# ardunio-physics-board-v1.net
KiCad netlist of a schematic drawn in EAGLE
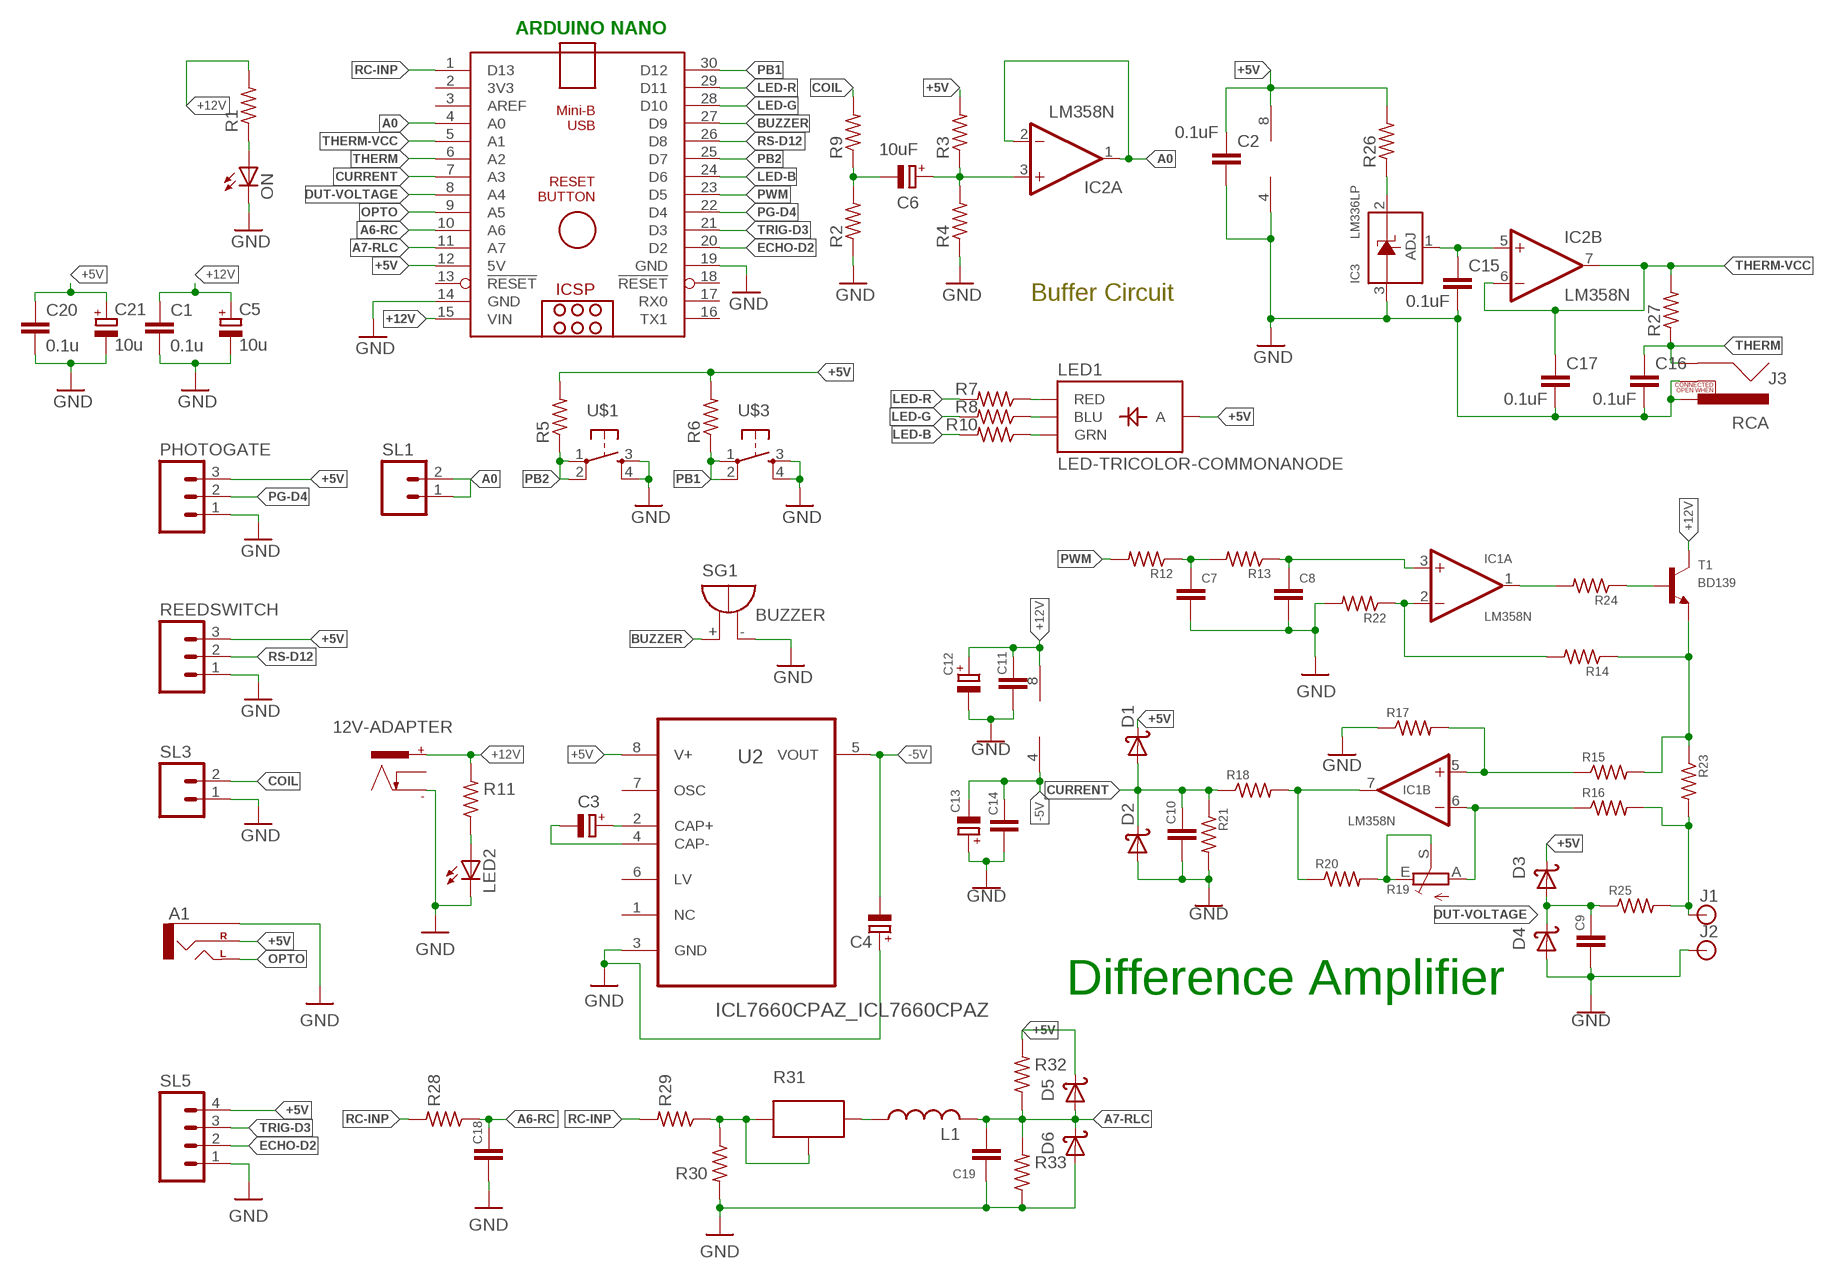
[diagram p0: schematic, sheet 1]

(export (version "E")
  (design (tool "Eeschema 10.0.6"))
  (components
    (comp (ref "12V-ADAPTER")
      (value "POWER_CON")
      (footprint "eagle-import:NEB21R")
      (libsource (lib "eagle-import") (part "POWER_CON"))
    )
    (comp (ref "A1")
      (value "CEDT_JANUARY_2015_V5_AUDIO-JACKPTH")
      (footprint "eagle-import:CEDT_JANUARY_2015_V5_AUDIO-JACK")
      (libsource (lib "eagle-import") (part "CEDT_JANUARY_2015_V5_AUDIO-JACKPTH"))
    )
    (comp (ref "ARDUINO_NANO1")
      (value "ARDUINO_NANO")
      (footprint "eagle-import:ARDUINO_NANO")
      (libsource (lib "eagle-import") (part "ARDUINO_NANO"))
    )
    (comp (ref "C1")
      (value "0.1u")
      (footprint "eagle-import:C025-024X044")
      (libsource (lib "eagle-import") (part "rcl_334_C-EU025-024X044"))
    )
    (comp (ref "C2")
      (value "0.1uF")
      (footprint "eagle-import:C025-025X050")
      (libsource (lib "eagle-import") (part "C-EU025-025X050"))
    )
    (comp (ref "C3")
      (value "CPOL-EUTT2D5")
      (footprint "eagle-import:TT2D5")
      (libsource (lib "eagle-import") (part "CPOL-EUTT2D5"))
    )
    (comp (ref "C4")
      (value "CPOL-EUTT2D5")
      (footprint "eagle-import:TT2D5")
      (libsource (lib "eagle-import") (part "CPOL-EUTT2D5"))
    )
    (comp (ref "C5")
      (value "10u")
      (footprint "eagle-import:E2,5-5")
      (libsource (lib "eagle-import") (part "CPOL-EUE2.5-5"))
    )
    (comp (ref "C6")
      (value "10uF")
      (footprint "eagle-import:E2,5-6")
      (libsource (lib "eagle-import") (part "CPOL-EUE2.5-6"))
    )
    (comp (ref "C7")
      (value "C-EU025-025X050")
      (footprint "eagle-import:C025-025X050")
      (libsource (lib "eagle-import") (part "rcl_334_C-EU025-025X050"))
    )
    (comp (ref "C8")
      (value "C-EU025-025X050")
      (footprint "eagle-import:C025-025X050")
      (libsource (lib "eagle-import") (part "rcl_334_C-EU025-025X050"))
    )
    (comp (ref "C9")
      (value "C-EU025-025X050")
      (footprint "eagle-import:C025-025X050")
      (libsource (lib "eagle-import") (part "rcl_334_C-EU025-025X050"))
    )
    (comp (ref "C10")
      (value "C-EU025-025X050")
      (footprint "eagle-import:C025-025X050")
      (libsource (lib "eagle-import") (part "rcl_334_C-EU025-025X050"))
    )
    (comp (ref "C11")
      (value "C-EU025-025X050")
      (footprint "eagle-import:C025-025X050")
      (libsource (lib "eagle-import") (part "rcl_334_C-EU025-025X050"))
    )
    (comp (ref "C12")
      (value "CPOL-EUTT2D5")
      (footprint "eagle-import:TT2D5")
      (libsource (lib "eagle-import") (part "CPOL-EUTT2D5"))
    )
    (comp (ref "C13")
      (value "CPOL-EUTT2D5")
      (footprint "eagle-import:TT2D5")
      (libsource (lib "eagle-import") (part "CPOL-EUTT2D5"))
    )
    (comp (ref "C14")
      (value "C-EU025-025X050")
      (footprint "eagle-import:C025-025X050")
      (libsource (lib "eagle-import") (part "rcl_334_C-EU025-025X050"))
    )
    (comp (ref "C15")
      (value "0.1uF")
      (footprint "eagle-import:C025-025X050")
      (libsource (lib "eagle-import") (part "C-EU025-025X050"))
    )
    (comp (ref "C16")
      (value "0.1uF")
      (footprint "eagle-import:C025-025X050")
      (libsource (lib "eagle-import") (part "C-EU025-025X050"))
    )
    (comp (ref "C17")
      (value "0.1uF")
      (footprint "eagle-import:C025-025X050")
      (libsource (lib "eagle-import") (part "C-EU025-025X050"))
    )
    (comp (ref "C18")
      (value "C-EU025-025X050")
      (footprint "eagle-import:C025-025X050")
      (libsource (lib "eagle-import") (part "rcl_334_C-EU025-025X050"))
    )
    (comp (ref "C19")
      (value "C-EU025-025X050")
      (footprint "eagle-import:C025-025X050")
      (libsource (lib "eagle-import") (part "rcl_334_C-EU025-025X050"))
    )
    (comp (ref "C20")
      (value "0.1u")
      (footprint "eagle-import:C025-024X044")
      (libsource (lib "eagle-import") (part "rcl_334_C-EU025-024X044"))
    )
    (comp (ref "C21")
      (value "10u")
      (footprint "eagle-import:E2,5-5")
      (libsource (lib "eagle-import") (part "CPOL-EUE2.5-5"))
    )
    (comp (ref "D1")
      (value "1N5819")
      (footprint "eagle-import:DO41-10")
      (libsource (lib "eagle-import") (part "1N5819"))
    )
    (comp (ref "D2")
      (value "1N5819")
      (footprint "eagle-import:DO41-10")
      (libsource (lib "eagle-import") (part "1N5819"))
    )
    (comp (ref "D3")
      (value "1N5819")
      (footprint "eagle-import:DO41-10")
      (libsource (lib "eagle-import") (part "1N5819"))
    )
    (comp (ref "D4")
      (value "1N5819")
      (footprint "eagle-import:DO41-10")
      (libsource (lib "eagle-import") (part "1N5819"))
    )
    (comp (ref "D5")
      (value "1N5819")
      (footprint "eagle-import:DO41-10")
      (libsource (lib "eagle-import") (part "1N5819"))
    )
    (comp (ref "D6")
      (value "1N5819")
      (footprint "eagle-import:DO41-10")
      (libsource (lib "eagle-import") (part "1N5819"))
    )
    (comp (ref "IC1")
      (value "LM358N")
      (footprint "eagle-import:DIL08")
      (libsource (lib "eagle-import") (part "LM358N"))
    )
    (comp (ref "IC2")
      (value "LM358N")
      (footprint "eagle-import:DIL08")
      (libsource (lib "eagle-import") (part "LM358N"))
    )
    (comp (ref "IC3")
      (value "LM336LP")
      (footprint "eagle-import:TO92")
      (libsource (lib "eagle-import") (part "LM336LP"))
    )
    (comp (ref "J1")
      (value "BANANA_CONN")
      (footprint "eagle-import:BANANA_CONN")
      (libsource (lib "eagle-import") (part "BANANA_CONN"))
    )
    (comp (ref "J2")
      (value "BANANA_CONN")
      (footprint "eagle-import:BANANA_CONN")
      (libsource (lib "eagle-import") (part "BANANA_CONN"))
    )
    (comp (ref "J3")
      (value "RCA")
      (footprint "eagle-import:RCA")
      (libsource (lib "eagle-import") (part "RCA"))
    )
    (comp (ref "L1")
      (value "L-US6000-XXX-RC")
      (footprint "eagle-import:6000-XXXX-RC")
      (libsource (lib "eagle-import") (part "L-US6000-XXX-RC"))
    )
    (comp (ref "LED1")
      (value "LED-TRICOLOR-COMMONANODE")
      (footprint "eagle-import:LED-TRICOLOR-THROUGHHOLE")
      (libsource (lib "eagle-import") (part "LED-TRICOLOR-COMMONANODE"))
    )
    (comp (ref "LED2")
      (value "LED3MM")
      (footprint "eagle-import:LED3MM")
      (libsource (lib "eagle-import") (part "CEDT_JANUARY_2015_v5_LED3MM"))
    )
    (comp (ref "ON")
      (value "LED3MM")
      (footprint "eagle-import:LED3MM")
      (libsource (lib "eagle-import") (part "LED3MM"))
    )
    (comp (ref "PHOTOGATE")
      (value "M03")
      (footprint "eagle-import:03P")
      (libsource (lib "eagle-import") (part "M03"))
    )
    (comp (ref "R1")
      (value "R-US_0204/7")
      (footprint "eagle-import:0204_7")
      (libsource (lib "eagle-import") (part "R-US_0204/7"))
    )
    (comp (ref "R2")
      (value "R-US_0204/7")
      (footprint "eagle-import:0204_7")
      (libsource (lib "eagle-import") (part "R-US_0204/7"))
    )
    (comp (ref "R3")
      (value "R-US_0204/7")
      (footprint "eagle-import:0204_7")
      (libsource (lib "eagle-import") (part "R-US_0204/7"))
    )
    (comp (ref "R4")
      (value "R-US_0204/7")
      (footprint "eagle-import:0204_7")
      (libsource (lib "eagle-import") (part "R-US_0204/7"))
    )
    (comp (ref "R5")
      (value "R-US_0204/7")
      (footprint "eagle-import:0204_7")
      (libsource (lib "eagle-import") (part "R-US_0204/7"))
    )
    (comp (ref "R6")
      (value "R-US_0204/7")
      (footprint "eagle-import:0204_7")
      (libsource (lib "eagle-import") (part "R-US_0204/7"))
    )
    (comp (ref "R7")
      (value "R-US_0204/7")
      (footprint "eagle-import:0204_7")
      (libsource (lib "eagle-import") (part "R-US_0204/7"))
    )
    (comp (ref "R8")
      (value "R-US_0204/7")
      (footprint "eagle-import:0204_7")
      (libsource (lib "eagle-import") (part "R-US_0204/7"))
    )
    (comp (ref "R9")
      (value "R-US_0204/7")
      (footprint "eagle-import:0204_7")
      (libsource (lib "eagle-import") (part "R-US_0204/7"))
    )
    (comp (ref "R10")
      (value "R-US_0204/7")
      (footprint "eagle-import:0204_7")
      (libsource (lib "eagle-import") (part "R-US_0204/7"))
    )
    (comp (ref "R11")
      (value "R-US_0204/7")
      (footprint "eagle-import:0204_7")
      (libsource (lib "eagle-import") (part "R-US_0204/7"))
    )
    (comp (ref "R12")
      (value "R-US_0204/7")
      (footprint "eagle-import:0204_7")
      (libsource (lib "eagle-import") (part "R-US_0204/7"))
    )
    (comp (ref "R13")
      (value "R-US_0204/7")
      (footprint "eagle-import:0204_7")
      (libsource (lib "eagle-import") (part "R-US_0204/7"))
    )
    (comp (ref "R14")
      (value "R-US_0204/7")
      (footprint "eagle-import:0204_7")
      (libsource (lib "eagle-import") (part "R-US_0204/7"))
    )
    (comp (ref "R15")
      (value "R-US_0204/7")
      (footprint "eagle-import:0204_7")
      (libsource (lib "eagle-import") (part "R-US_0204/7"))
    )
    (comp (ref "R16")
      (value "R-US_0204/7")
      (footprint "eagle-import:0204_7")
      (libsource (lib "eagle-import") (part "R-US_0204/7"))
    )
    (comp (ref "R17")
      (value "R-US_0204/7")
      (footprint "eagle-import:0204_7")
      (libsource (lib "eagle-import") (part "R-US_0204/7"))
    )
    (comp (ref "R18")
      (value "R-US_0204/7")
      (footprint "eagle-import:0204_7")
      (libsource (lib "eagle-import") (part "R-US_0204/7"))
    )
    (comp (ref "R19")
      (value "TRIM_EU-RJ9W")
      (footprint "eagle-import:RJ9W")
      (libsource (lib "eagle-import") (part "TRIM_EU-RJ9W"))
    )
    (comp (ref "R20")
      (value "R-US_0204/7")
      (footprint "eagle-import:0204_7")
      (libsource (lib "eagle-import") (part "R-US_0204/7"))
    )
    (comp (ref "R21")
      (value "R-US_0204/7")
      (footprint "eagle-import:0204_7")
      (libsource (lib "eagle-import") (part "R-US_0204/7"))
    )
    (comp (ref "R22")
      (value "R-US_0204/7")
      (footprint "eagle-import:0204_7")
      (libsource (lib "eagle-import") (part "R-US_0204/7"))
    )
    (comp (ref "R23")
      (value "R-US_0207/10")
      (footprint "eagle-import:0207_10")
      (libsource (lib "eagle-import") (part "R-US_0207/10"))
    )
    (comp (ref "R24")
      (value "R-US_0204/7")
      (footprint "eagle-import:0204_7")
      (libsource (lib "eagle-import") (part "R-US_0204/7"))
    )
    (comp (ref "R25")
      (value "R-US_0204/7")
      (footprint "eagle-import:0204_7")
      (libsource (lib "eagle-import") (part "R-US_0204/7"))
    )
    (comp (ref "R26")
      (value "R-US_0204/7")
      (footprint "eagle-import:0204_7")
      (libsource (lib "eagle-import") (part "R-US_0204/7"))
    )
    (comp (ref "R27")
      (value "R-US_0204/7")
      (footprint "eagle-import:0204_7")
      (libsource (lib "eagle-import") (part "R-US_0204/7"))
    )
    (comp (ref "R28")
      (value "R-US_0204/7")
      (footprint "eagle-import:0204_7")
      (libsource (lib "eagle-import") (part "R-US_0204/7"))
    )
    (comp (ref "R29")
      (value "R-US_0204/7")
      (footprint "eagle-import:0204_7")
      (libsource (lib "eagle-import") (part "R-US_0204/7"))
    )
    (comp (ref "R30")
      (value "R-US_0204/7")
      (footprint "eagle-import:0204_7")
      (libsource (lib "eagle-import") (part "R-US_0204/7"))
    )
    (comp (ref "R31")
      (value "POTNORMAL")
      (footprint "eagle-import:RJ9W")
      (libsource (lib "eagle-import") (part "POTNORMAL"))
    )
    (comp (ref "R32")
      (value "R-US_0204/7")
      (footprint "eagle-import:0204_7")
      (libsource (lib "eagle-import") (part "R-US_0204/7"))
    )
    (comp (ref "R33")
      (value "R-US_0204/7")
      (footprint "eagle-import:0204_7")
      (libsource (lib "eagle-import") (part "R-US_0204/7"))
    )
    (comp (ref "REEDSWITCH")
      (value "M03")
      (footprint "eagle-import:03P")
      (libsource (lib "eagle-import") (part "M03"))
    )
    (comp (ref "SG1")
      (value "BUZZER")
      (footprint "eagle-import:F_TMB")
      (libsource (lib "eagle-import") (part "BUZZER"))
    )
    (comp (ref "SL1")
      (value "M02")
      (footprint "eagle-import:02P")
      (libsource (lib "eagle-import") (part "M02"))
    )
    (comp (ref "SL3")
      (value "M02")
      (footprint "eagle-import:02P")
      (libsource (lib "eagle-import") (part "M02"))
    )
    (comp (ref "SL5")
      (value "M04")
      (footprint "eagle-import:04P")
      (libsource (lib "eagle-import") (part "M04"))
    )
    (comp (ref "T1")
      (value "BD139")
      (footprint "eagle-import:TO126")
      (libsource (lib "eagle-import") (part "BD139"))
    )
    (comp (ref "U$1")
      (value "OMRON_SWITCH_40-XX")
      (footprint "eagle-import:B3F-40XX")
      (libsource (lib "eagle-import") (part "OMRON_SWITCH_40-XX"))
    )
    (comp (ref "U$3")
      (value "OMRON_SWITCH_40-XX")
      (footprint "eagle-import:B3F-40XX")
      (libsource (lib "eagle-import") (part "OMRON_SWITCH_40-XX"))
    )
    (comp (ref "U2")
      (value "ICL7660CPAZ_ICL7660CPAZ")
      (footprint "eagle-import:ICL7660CPAZ_DIP254P762X533-8")
      (fields (field (name "MF") "Renesas Electronics") (field (name "MP") "ICL7660CPAZ"))
      (libsource (lib "eagle-import") (part "ICL7660CPAZ_ICL7660CPAZ"))
    )
  )
  (nets
    (net (code "1") (name "+5V") (class "Default")
      (node (ref "A1") (pin "RING") (pinfunction "RIGHT_RING") (pintype "bidirectional"))
      (node (ref "ARDUINO_NANO1") (pin "12") (pinfunction "5V_12") (pintype "power_in"))
      (node (ref "C2") (pin "1") (pinfunction "1_1") (pintype "passive"))
      (node (ref "C20") (pin "1") (pinfunction "1_1") (pintype "passive"))
      (node (ref "C21") (pin "+") (pinfunction "+_+") (pintype "passive"))
      (node (ref "D1") (pin "C") (pinfunction "C_C") (pintype "passive"))
      (node (ref "D3") (pin "C") (pinfunction "C_C") (pintype "passive"))
      (node (ref "D5") (pin "C") (pinfunction "C_C") (pintype "passive"))
      (node (ref "IC2") (pin "8") (pinfunction "V+_8") (pintype "power_in"))
      (node (ref "LED1") (pin "ANODE") (pinfunction "A_ANODE") (pintype "bidirectional"))
      (node (ref "PHOTOGATE") (pin "3") (pinfunction "3_3") (pintype "passive"))
      (node (ref "R26") (pin "2") (pinfunction "2_2") (pintype "passive"))
      (node (ref "R3") (pin "2") (pinfunction "2_2") (pintype "passive"))
      (node (ref "R32") (pin "2") (pinfunction "2_2") (pintype "passive"))
      (node (ref "R5") (pin "2") (pinfunction "2_2") (pintype "passive"))
      (node (ref "R6") (pin "2") (pinfunction "2_2") (pintype "passive"))
      (node (ref "REEDSWITCH") (pin "3") (pinfunction "3_3") (pintype "passive"))
      (node (ref "SL5") (pin "4") (pinfunction "4_4") (pintype "passive"))
      (node (ref "U2") (pin "8") (pinfunction "V+_8") (pintype "power_in"))
    )
    (net (code "2") (name "+12V") (class "Default")
      (node (ref "12V-ADAPTER") (pin "+") (pinfunction "+_+") (pintype "passive"))
      (node (ref "ARDUINO_NANO1") (pin "15") (pinfunction "VIN_15") (pintype "power_in"))
      (node (ref "C1") (pin "1") (pinfunction "1_1") (pintype "passive"))
      (node (ref "C11") (pin "1") (pinfunction "1_1") (pintype "passive"))
      (node (ref "C12") (pin "+") (pinfunction "+_+") (pintype "passive"))
      (node (ref "C5") (pin "+") (pinfunction "+_+") (pintype "passive"))
      (node (ref "IC1") (pin "8") (pinfunction "V+_8") (pintype "power_in"))
      (node (ref "R1") (pin "2") (pinfunction "2_2") (pintype "passive"))
      (node (ref "R11") (pin "2") (pinfunction "2_2") (pintype "passive"))
      (node (ref "T1") (pin "2") (pinfunction "C_2") (pintype "passive"))
    )
    (net (code "3") (name "-5V") (class "Default")
      (node (ref "C13") (pin "-") (pinfunction "-_-") (pintype "passive"))
      (node (ref "C14") (pin "1") (pinfunction "1_1") (pintype "passive"))
      (node (ref "C4") (pin "-") (pinfunction "-_-") (pintype "passive"))
      (node (ref "IC1") (pin "4") (pinfunction "V-_4") (pintype "power_in"))
      (node (ref "U2") (pin "5") (pinfunction "VOUT_5") (pintype "output"))
    )
    (net (code "4") (name "A0") (class "Default")
      (node (ref "ARDUINO_NANO1") (pin "4") (pinfunction "A0_4") (pintype "bidirectional"))
      (node (ref "IC2") (pin "1") (pinfunction "OUT_1") (pintype "output"))
      (node (ref "IC2") (pin "2") (pinfunction "-IN_2") (pintype "input"))
      (node (ref "SL1") (pin "1") (pinfunction "1_1") (pintype "passive"))
      (node (ref "SL1") (pin "2") (pinfunction "2_2") (pintype "passive"))
    )
    (net (code "5") (name "A6-RC") (class "Default")
      (node (ref "ARDUINO_NANO1") (pin "10") (pinfunction "A6_10") (pintype "bidirectional"))
      (node (ref "C18") (pin "1") (pinfunction "1_1") (pintype "passive"))
      (node (ref "R28") (pin "1") (pinfunction "1_1") (pintype "passive"))
    )
    (net (code "6") (name "A7-RLC") (class "Default")
      (node (ref "ARDUINO_NANO1") (pin "11") (pinfunction "A7_11") (pintype "bidirectional"))
      (node (ref "C19") (pin "1") (pinfunction "1_1") (pintype "passive"))
      (node (ref "D5") (pin "A") (pinfunction "A_A") (pintype "passive"))
      (node (ref "D6") (pin "C") (pinfunction "C_C") (pintype "passive"))
      (node (ref "L1") (pin "2") (pinfunction "2_2") (pintype "passive"))
      (node (ref "R32") (pin "1") (pinfunction "1_1") (pintype "passive"))
      (node (ref "R33") (pin "2") (pinfunction "2_2") (pintype "passive"))
    )
    (net (code "7") (name "BUZZER") (class "Default")
      (node (ref "ARDUINO_NANO1") (pin "27") (pinfunction "D9_27") (pintype "bidirectional"))
      (node (ref "SG1") (pin "+") (pinfunction "+_+") (pintype "passive"))
    )
    (net (code "8") (name "COIL") (class "Default")
      (node (ref "R9") (pin "2") (pinfunction "2_2") (pintype "passive"))
      (node (ref "SL3") (pin "2") (pinfunction "2_2") (pintype "passive"))
    )
    (net (code "9") (name "CURRENT") (class "Default")
      (node (ref "ARDUINO_NANO1") (pin "7") (pinfunction "A3_7") (pintype "bidirectional"))
      (node (ref "C10") (pin "1") (pinfunction "1_1") (pintype "passive"))
      (node (ref "D1") (pin "A") (pinfunction "A_A") (pintype "passive"))
      (node (ref "D2") (pin "C") (pinfunction "C_C") (pintype "passive"))
      (node (ref "R18") (pin "1") (pinfunction "1_1") (pintype "passive"))
      (node (ref "R21") (pin "1") (pinfunction "1_1") (pintype "passive"))
    )
    (net (code "10") (name "DUT-VOLTAGE") (class "Default")
      (node (ref "ARDUINO_NANO1") (pin "8") (pinfunction "A4_8") (pintype "bidirectional"))
      (node (ref "C9") (pin "1") (pinfunction "1_1") (pintype "passive"))
      (node (ref "D3") (pin "A") (pinfunction "A_A") (pintype "passive"))
      (node (ref "D4") (pin "C") (pinfunction "C_C") (pintype "passive"))
      (node (ref "R25") (pin "1") (pinfunction "1_1") (pintype "passive"))
    )
    (net (code "11") (name "ECHO-D2") (class "Default")
      (node (ref "ARDUINO_NANO1") (pin "20") (pinfunction "D2_20") (pintype "bidirectional"))
      (node (ref "SL5") (pin "2") (pinfunction "2_2") (pintype "passive"))
    )
    (net (code "12") (name "GND") (class "Default")
      (node (ref "12V-ADAPTER") (pin "-") (pinfunction "-_-") (pintype "passive"))
      (node (ref "A1") (pin "SLEEVE") (pinfunction "SLEEVE_SLEEVE") (pintype "bidirectional"))
      (node (ref "ARDUINO_NANO1") (pin "14") (pinfunction "GND_14") (pintype "power_in"))
      (node (ref "ARDUINO_NANO1") (pin "19") (pinfunction "GND_19") (pintype "power_in"))
      (node (ref "C1") (pin "2") (pinfunction "2_2") (pintype "passive"))
      (node (ref "C10") (pin "2") (pinfunction "2_2") (pintype "passive"))
      (node (ref "C11") (pin "2") (pinfunction "2_2") (pintype "passive"))
      (node (ref "C12") (pin "-") (pinfunction "-_-") (pintype "passive"))
      (node (ref "C13") (pin "+") (pinfunction "+_+") (pintype "passive"))
      (node (ref "C14") (pin "2") (pinfunction "2_2") (pintype "passive"))
      (node (ref "C15") (pin "2") (pinfunction "2_2") (pintype "passive"))
      (node (ref "C16") (pin "2") (pinfunction "2_2") (pintype "passive"))
      (node (ref "C17") (pin "2") (pinfunction "2_2") (pintype "passive"))
      (node (ref "C18") (pin "2") (pinfunction "2_2") (pintype "passive"))
      (node (ref "C19") (pin "2") (pinfunction "2_2") (pintype "passive"))
      (node (ref "C2") (pin "2") (pinfunction "2_2") (pintype "passive"))
      (node (ref "C20") (pin "2") (pinfunction "2_2") (pintype "passive"))
      (node (ref "C21") (pin "-") (pinfunction "-_-") (pintype "passive"))
      (node (ref "C4") (pin "+") (pinfunction "+_+") (pintype "passive"))
      (node (ref "C5") (pin "-") (pinfunction "-_-") (pintype "passive"))
      (node (ref "C7") (pin "2") (pinfunction "2_2") (pintype "passive"))
      (node (ref "C8") (pin "2") (pinfunction "2_2") (pintype "passive"))
      (node (ref "C9") (pin "2") (pinfunction "2_2") (pintype "passive"))
      (node (ref "D2") (pin "A") (pinfunction "A_A") (pintype "passive"))
      (node (ref "D4") (pin "A") (pinfunction "A_A") (pintype "passive"))
      (node (ref "D6") (pin "A") (pinfunction "A_A") (pintype "passive"))
      (node (ref "IC2") (pin "4") (pinfunction "V-_4") (pintype "power_in"))
      (node (ref "IC3") (pin "3") (pinfunction "A_3") (pintype "input"))
      (node (ref "J2") (pin "P$1") (pinfunction "1_P$1") (pintype "passive"))
      (node (ref "J3") (pin "PIN") (pinfunction "PIN_PIN") (pintype "bidirectional"))
      (node (ref "J3") (pin "SWITCH") (pinfunction "SWITCH_SWITCH") (pintype "bidirectional"))
      (node (ref "LED2") (pin "K") (pinfunction "C_K") (pintype "passive"))
      (node (ref "ON") (pin "K") (pinfunction "C_K") (pintype "passive"))
      (node (ref "PHOTOGATE") (pin "1") (pinfunction "1_1") (pintype "passive"))
      (node (ref "R17") (pin "1") (pinfunction "1_1") (pintype "passive"))
      (node (ref "R2") (pin "1") (pinfunction "1_1") (pintype "passive"))
      (node (ref "R21") (pin "2") (pinfunction "2_2") (pintype "passive"))
      (node (ref "R22") (pin "2") (pinfunction "2_2") (pintype "passive"))
      (node (ref "R30") (pin "2") (pinfunction "2_2") (pintype "passive"))
      (node (ref "R33") (pin "1") (pinfunction "1_1") (pintype "passive"))
      (node (ref "R4") (pin "1") (pinfunction "1_1") (pintype "passive"))
      (node (ref "REEDSWITCH") (pin "1") (pinfunction "1_1") (pintype "passive"))
      (node (ref "SG1") (pin "-") (pinfunction "-_-") (pintype "passive"))
      (node (ref "SL3") (pin "1") (pinfunction "1_1") (pintype "passive"))
      (node (ref "SL5") (pin "1") (pinfunction "1_1") (pintype "passive"))
      (node (ref "U$1") (pin "3") (pinfunction "S_3") (pintype "passive"))
      (node (ref "U$1") (pin "4") (pinfunction "S1_4") (pintype "passive"))
      (node (ref "U$3") (pin "3") (pinfunction "S_3") (pintype "passive"))
      (node (ref "U$3") (pin "4") (pinfunction "S1_4") (pintype "passive"))
      (node (ref "U2") (pin "3") (pinfunction "GND_3") (pintype "passive"))
    )
    (net (code "13") (name "LED-B") (class "Default")
      (node (ref "ARDUINO_NANO1") (pin "24") (pinfunction "D6_24") (pintype "bidirectional"))
      (node (ref "R10") (pin "2") (pinfunction "2_2") (pintype "passive"))
    )
    (net (code "14") (name "LED-G") (class "Default")
      (node (ref "ARDUINO_NANO1") (pin "28") (pinfunction "D10_28") (pintype "bidirectional"))
      (node (ref "R8") (pin "2") (pinfunction "2_2") (pintype "passive"))
    )
    (net (code "15") (name "LED-R") (class "Default")
      (node (ref "ARDUINO_NANO1") (pin "29") (pinfunction "D11_29") (pintype "bidirectional"))
      (node (ref "R7") (pin "2") (pinfunction "2_2") (pintype "passive"))
    )
    (net (code "16") (name "Net-(C6-Pad-)") (class "Default")
      (node (ref "C6") (pin "-") (pinfunction "-_-") (pintype "passive"))
      (node (ref "R2") (pin "2") (pinfunction "2_2") (pintype "passive"))
      (node (ref "R9") (pin "1") (pinfunction "1_1") (pintype "passive"))
    )
    (net (code "17") (name "Net-(C7-Pad1)") (class "Default")
      (node (ref "C7") (pin "1") (pinfunction "1_1") (pintype "passive"))
      (node (ref "R12") (pin "1") (pinfunction "1_1") (pintype "passive"))
      (node (ref "R13") (pin "2") (pinfunction "2_2") (pintype "passive"))
    )
    (net (code "18") (name "Net-(IC1A-+IN)") (class "Default")
      (node (ref "C8") (pin "1") (pinfunction "1_1") (pintype "passive"))
      (node (ref "IC1") (pin "3") (pinfunction "+IN_3") (pintype "input"))
      (node (ref "R13") (pin "1") (pinfunction "1_1") (pintype "passive"))
    )
    (net (code "19") (name "Net-(IC1A--IN)") (class "Default")
      (node (ref "IC1") (pin "2") (pinfunction "-IN_2") (pintype "input"))
      (node (ref "R14") (pin "2") (pinfunction "2_2") (pintype "passive"))
      (node (ref "R22") (pin "1") (pinfunction "1_1") (pintype "passive"))
    )
    (net (code "20") (name "Net-(IC1A-OUT)") (class "Default")
      (node (ref "IC1") (pin "1") (pinfunction "OUT_1") (pintype "output"))
      (node (ref "R24") (pin "2") (pinfunction "2_2") (pintype "passive"))
    )
    (net (code "21") (name "Net-(IC1B-+IN)") (class "Default")
      (node (ref "IC1") (pin "5") (pinfunction "+IN_5") (pintype "input"))
      (node (ref "R15") (pin "1") (pinfunction "1_1") (pintype "passive"))
      (node (ref "R17") (pin "2") (pinfunction "2_2") (pintype "passive"))
    )
    (net (code "22") (name "Net-(IC1B--IN)") (class "Default")
      (node (ref "IC1") (pin "6") (pinfunction "-IN_6") (pintype "input"))
      (node (ref "R16") (pin "1") (pinfunction "1_1") (pintype "passive"))
      (node (ref "R19") (pin "A") (pinfunction "A_A") (pintype "passive"))
    )
    (net (code "23") (name "Net-(IC1B-OUT)") (class "Default")
      (node (ref "IC1") (pin "7") (pinfunction "OUT_7") (pintype "output"))
      (node (ref "R18") (pin "2") (pinfunction "2_2") (pintype "passive"))
      (node (ref "R20") (pin "1") (pinfunction "1_1") (pintype "passive"))
    )
    (net (code "24") (name "Net-(IC2A-+IN)") (class "Default")
      (node (ref "C6") (pin "+") (pinfunction "+_+") (pintype "passive"))
      (node (ref "IC2") (pin "3") (pinfunction "+IN_3") (pintype "input"))
      (node (ref "R3") (pin "1") (pinfunction "1_1") (pintype "passive"))
      (node (ref "R4") (pin "2") (pinfunction "2_2") (pintype "passive"))
    )
    (net (code "25") (name "Net-(IC2B-+IN)") (class "Default")
      (node (ref "C15") (pin "1") (pinfunction "1_1") (pintype "passive"))
      (node (ref "IC2") (pin "5") (pinfunction "+IN_5") (pintype "input"))
      (node (ref "IC3") (pin "1") (pinfunction "ADJ_1") (pintype "input"))
    )
    (net (code "26") (name "Net-(IC3-C)") (class "Default")
      (node (ref "IC3") (pin "2") (pinfunction "C_2") (pintype "passive"))
      (node (ref "R26") (pin "1") (pinfunction "1_1") (pintype "passive"))
    )
    (net (code "27") (name "Net-(J1-1)") (class "Default")
      (node (ref "J1") (pin "P$1") (pinfunction "1_P$1") (pintype "passive"))
      (node (ref "R16") (pin "2") (pinfunction "2_2") (pintype "passive"))
      (node (ref "R23") (pin "2") (pinfunction "2_2") (pintype "passive"))
      (node (ref "R25") (pin "2") (pinfunction "2_2") (pintype "passive"))
    )
    (net (code "28") (name "Net-(L1-Pad1)") (class "Default")
      (node (ref "L1") (pin "1") (pinfunction "1_1") (pintype "passive"))
      (node (ref "R31") (pin "A") (pinfunction "A_A") (pintype "passive"))
    )
    (net (code "29") (name "Net-(LED1-PadBLU)") (class "Default")
      (node (ref "LED1") (pin "BLU") (pinfunction "BLU_BLU") (pintype "bidirectional"))
      (node (ref "R8") (pin "1") (pinfunction "1_1") (pintype "passive"))
    )
    (net (code "30") (name "Net-(LED1-PadGRN)") (class "Default")
      (node (ref "LED1") (pin "GRN") (pinfunction "GRN_GRN") (pintype "bidirectional"))
      (node (ref "R10") (pin "1") (pinfunction "1_1") (pintype "passive"))
    )
    (net (code "31") (name "Net-(LED1-PadRED)") (class "Default")
      (node (ref "LED1") (pin "RED") (pinfunction "RED_RED") (pintype "bidirectional"))
      (node (ref "R7") (pin "1") (pinfunction "1_1") (pintype "passive"))
    )
    (net (code "32") (name "Net-(LED2-PadA)") (class "Default")
      (node (ref "LED2") (pin "A") (pinfunction "A_A") (pintype "passive"))
      (node (ref "R11") (pin "1") (pinfunction "1_1") (pintype "passive"))
    )
    (net (code "33") (name "Net-(ON-PadA)") (class "Default")
      (node (ref "ON") (pin "A") (pinfunction "A_A") (pintype "passive"))
      (node (ref "R1") (pin "1") (pinfunction "1_1") (pintype "passive"))
    )
    (net (code "34") (name "Net-(R19-PadE)") (class "Default")
      (node (ref "R19") (pin "E") (pinfunction "E_E") (pintype "passive"))
      (node (ref "R19") (pin "S") (pinfunction "S_S") (pintype "passive"))
      (node (ref "R20") (pin "2") (pinfunction "2_2") (pintype "passive"))
    )
    (net (code "35") (name "Net-(R29-Pad1)") (class "Default")
      (node (ref "R29") (pin "1") (pinfunction "1_1") (pintype "passive"))
      (node (ref "R30") (pin "1") (pinfunction "1_1") (pintype "passive"))
      (node (ref "R31") (pin "E") (pinfunction "E_E") (pintype "passive"))
      (node (ref "R31") (pin "S") (pinfunction "S_S") (pintype "passive"))
    )
    (net (code "36") (name "Net-(T1-B)") (class "Default")
      (node (ref "R24") (pin "1") (pinfunction "1_1") (pintype "passive"))
      (node (ref "T1") (pin "3") (pinfunction "B_3") (pintype "passive"))
    )
    (net (code "37") (name "Net-(T1-E)") (class "Default")
      (node (ref "R14") (pin "1") (pinfunction "1_1") (pintype "passive"))
      (node (ref "R15") (pin "2") (pinfunction "2_2") (pintype "passive"))
      (node (ref "R23") (pin "1") (pinfunction "1_1") (pintype "passive"))
      (node (ref "T1") (pin "1") (pinfunction "E_1") (pintype "passive"))
    )
    (net (code "38") (name "Net-(U2-CAP+)") (class "Default")
      (node (ref "C3") (pin "+") (pinfunction "+_+") (pintype "passive"))
      (node (ref "U2") (pin "2") (pinfunction "CAP+_2") (pintype "input"))
    )
    (net (code "39") (name "Net-(U2-CAP-)") (class "Default")
      (node (ref "C3") (pin "-") (pinfunction "-_-") (pintype "passive"))
      (node (ref "U2") (pin "4") (pinfunction "CAP-_4") (pintype "input"))
    )
    (net (code "40") (name "OPTO") (class "Default")
      (node (ref "A1") (pin "TIP") (pinfunction "LEFT_TIP") (pintype "bidirectional"))
      (node (ref "ARDUINO_NANO1") (pin "9") (pinfunction "A5_9") (pintype "bidirectional"))
    )
    (net (code "41") (name "PB1") (class "Default")
      (node (ref "ARDUINO_NANO1") (pin "30") (pinfunction "D12_30") (pintype "bidirectional"))
      (node (ref "R6") (pin "1") (pinfunction "1_1") (pintype "passive"))
      (node (ref "U$3") (pin "1") (pinfunction "P_1") (pintype "passive"))
      (node (ref "U$3") (pin "2") (pinfunction "P1_2") (pintype "passive"))
    )
    (net (code "42") (name "PB2") (class "Default")
      (node (ref "ARDUINO_NANO1") (pin "25") (pinfunction "D7_25") (pintype "bidirectional"))
      (node (ref "R5") (pin "1") (pinfunction "1_1") (pintype "passive"))
      (node (ref "U$1") (pin "1") (pinfunction "P_1") (pintype "passive"))
      (node (ref "U$1") (pin "2") (pinfunction "P1_2") (pintype "passive"))
    )
    (net (code "43") (name "PG-D4") (class "Default")
      (node (ref "ARDUINO_NANO1") (pin "22") (pinfunction "D4_22") (pintype "bidirectional"))
      (node (ref "PHOTOGATE") (pin "2") (pinfunction "2_2") (pintype "passive"))
    )
    (net (code "44") (name "PWM") (class "Default")
      (node (ref "ARDUINO_NANO1") (pin "23") (pinfunction "D5_23") (pintype "bidirectional"))
      (node (ref "R12") (pin "2") (pinfunction "2_2") (pintype "passive"))
    )
    (net (code "45") (name "RC-INP") (class "Default")
      (node (ref "ARDUINO_NANO1") (pin "1") (pinfunction "D13_1") (pintype "bidirectional"))
      (node (ref "R28") (pin "2") (pinfunction "2_2") (pintype "passive"))
      (node (ref "R29") (pin "2") (pinfunction "2_2") (pintype "passive"))
    )
    (net (code "46") (name "RS-D12") (class "Default")
      (node (ref "ARDUINO_NANO1") (pin "26") (pinfunction "D8_26") (pintype "bidirectional"))
      (node (ref "REEDSWITCH") (pin "2") (pinfunction "2_2") (pintype "passive"))
    )
    (net (code "47") (name "THERM") (class "Default")
      (node (ref "ARDUINO_NANO1") (pin "6") (pinfunction "A2_6") (pintype "bidirectional"))
      (node (ref "C16") (pin "1") (pinfunction "1_1") (pintype "passive"))
      (node (ref "J3") (pin "SHELL") (pinfunction "SHELL_SHELL") (pintype "bidirectional"))
      (node (ref "R27") (pin "1") (pinfunction "1_1") (pintype "passive"))
    )
    (net (code "48") (name "THERM-VCC") (class "Default")
      (node (ref "ARDUINO_NANO1") (pin "5") (pinfunction "A1_5") (pintype "bidirectional"))
      (node (ref "C17") (pin "1") (pinfunction "1_1") (pintype "passive"))
      (node (ref "IC2") (pin "6") (pinfunction "-IN_6") (pintype "input"))
      (node (ref "IC2") (pin "7") (pinfunction "OUT_7") (pintype "output"))
      (node (ref "R27") (pin "2") (pinfunction "2_2") (pintype "passive"))
    )
    (net (code "49") (name "TRIG-D3") (class "Default")
      (node (ref "ARDUINO_NANO1") (pin "21") (pinfunction "D3_21") (pintype "bidirectional"))
      (node (ref "SL5") (pin "3") (pinfunction "3_3") (pintype "passive"))
    )
    (net (code "50") (name "unconnected-(12V-ADAPTER-PadC)") (class "Default")
      (node (ref "12V-ADAPTER") (pin "C") (pinfunction "C_C") (pintype "passive"))
    )
    (net (code "51") (name "unconnected-(ARDUINO_NANO1-3V3-Pad2)") (class "Default")
      (node (ref "ARDUINO_NANO1") (pin "2") (pinfunction "3V3_2") (pintype "output"))
    )
    (net (code "52") (name "unconnected-(ARDUINO_NANO1-AREF-Pad3)") (class "Default")
      (node (ref "ARDUINO_NANO1") (pin "3") (pinfunction "AREF_3") (pintype "input"))
    )
    (net (code "53") (name "unconnected-(ARDUINO_NANO1-RX0-Pad17)") (class "Default")
      (node (ref "ARDUINO_NANO1") (pin "17") (pinfunction "RX0_17") (pintype "bidirectional"))
    )
    (net (code "54") (name "unconnected-(ARDUINO_NANO1-TX1-Pad16)") (class "Default")
      (node (ref "ARDUINO_NANO1") (pin "16") (pinfunction "TX1_16") (pintype "bidirectional"))
    )
    (net (code "55") (name "unconnected-(ARDUINO_NANO1-~{RESET}-Pad13)") (class "Default")
      (node (ref "ARDUINO_NANO1") (pin "13") (pinfunction "~{RESET}_13") (pintype "input"))
    )
    (net (code "56") (name "unconnected-(ARDUINO_NANO1-~{RESET}-Pad18)") (class "Default")
      (node (ref "ARDUINO_NANO1") (pin "18") (pinfunction "~{RESET}_18") (pintype "input"))
    )
    (net (code "57") (name "unconnected-(U2-LV-Pad6)") (class "Default")
      (node (ref "U2") (pin "6") (pinfunction "LV_6") (pintype "passive"))
    )
    (net (code "58") (name "unconnected-(U2-NC-Pad1)") (class "Default")
      (node (ref "U2") (pin "1") (pinfunction "NC_1") (pintype "no_connect"))
    )
    (net (code "59") (name "unconnected-(U2-OSC-Pad7)") (class "Default")
      (node (ref "U2") (pin "7") (pinfunction "OSC_7") (pintype "input"))
    )
  )
)
